# ESP-12E_Dev_Board_with_level_shifter.net
KiCad netlist of a schematic drawn in EAGLE
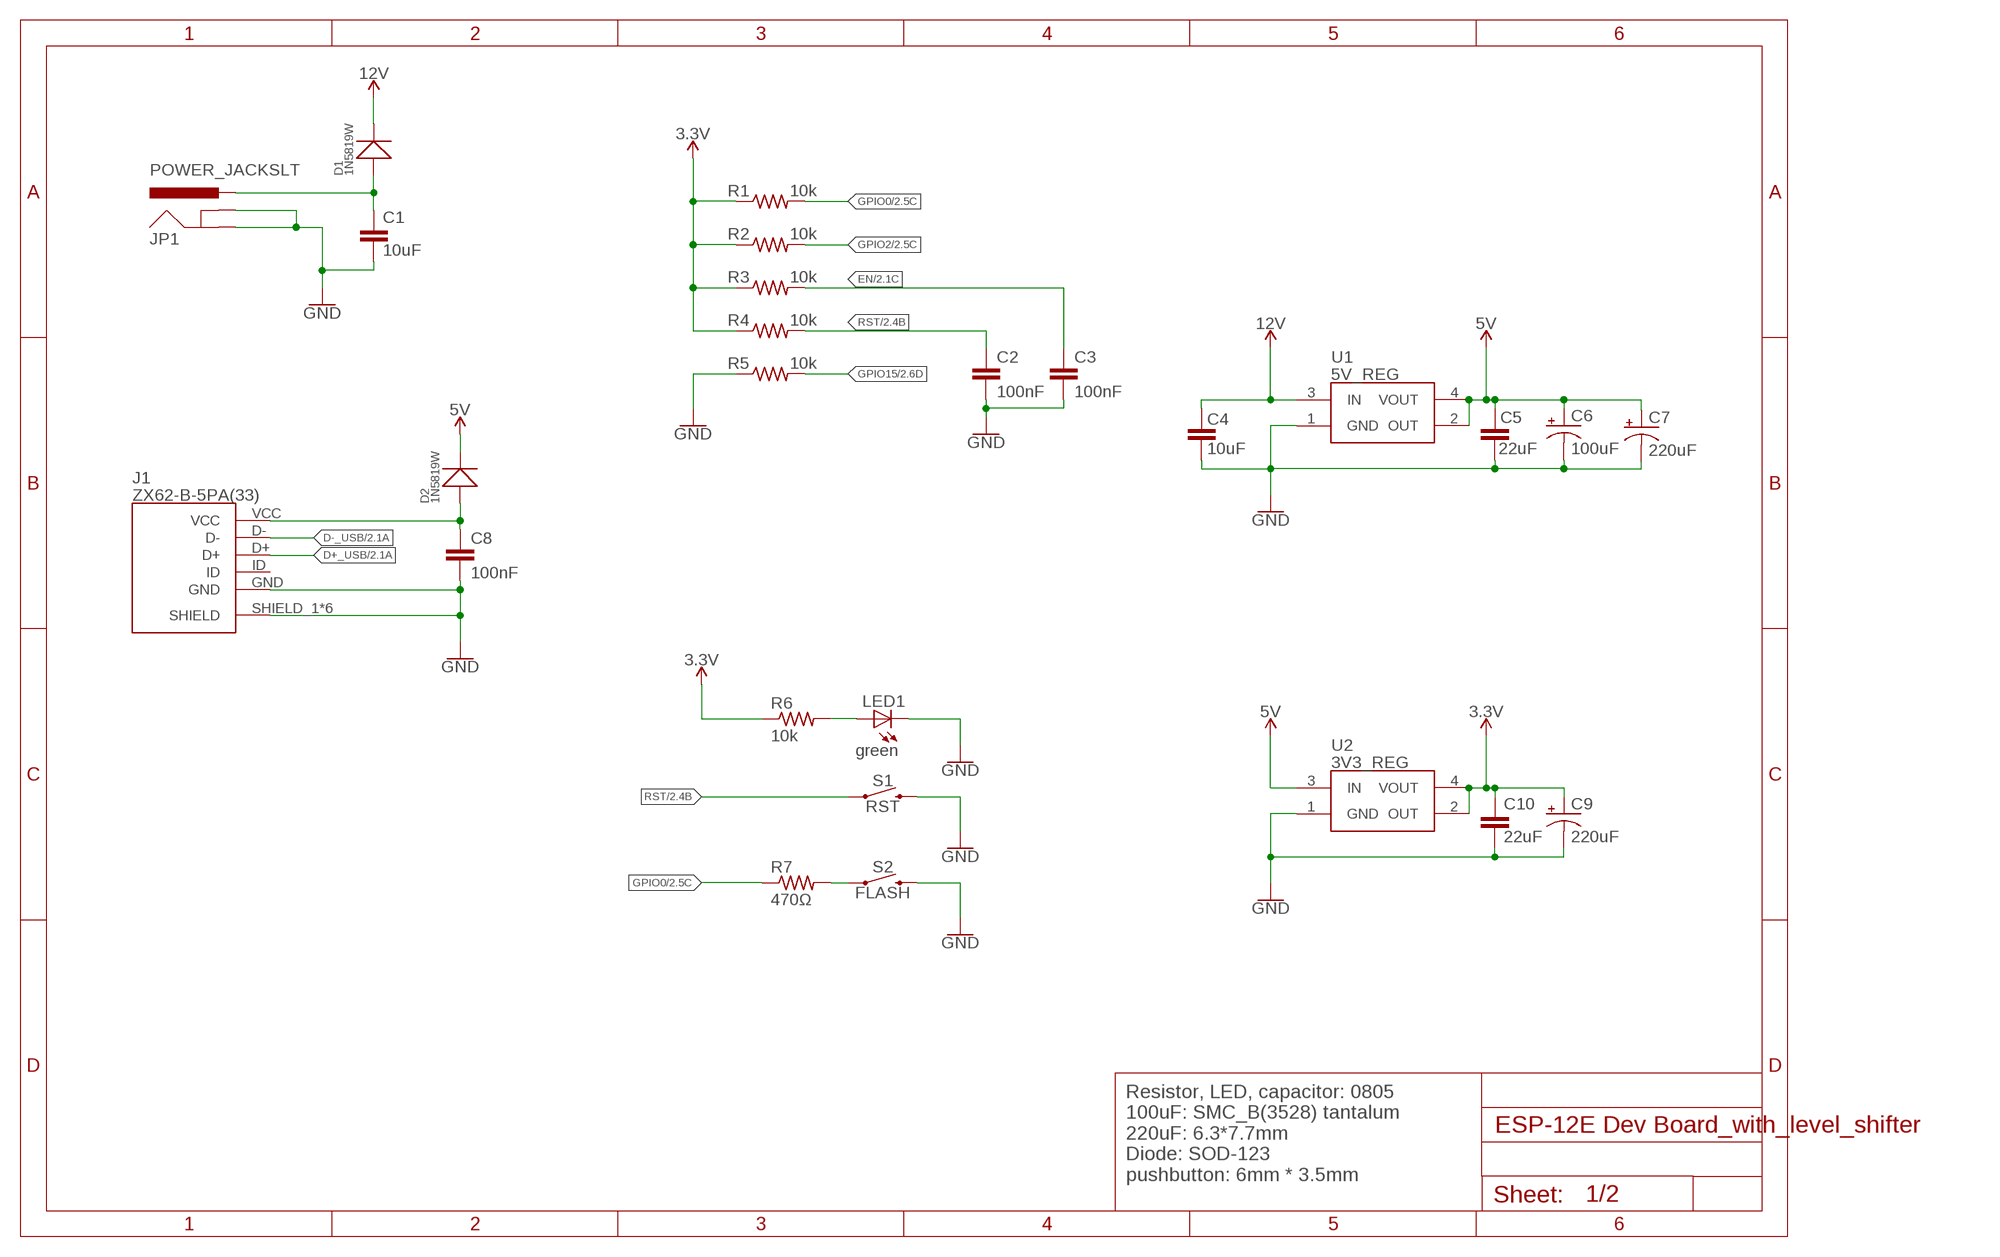
[diagram p0: schematic, sheet 1]
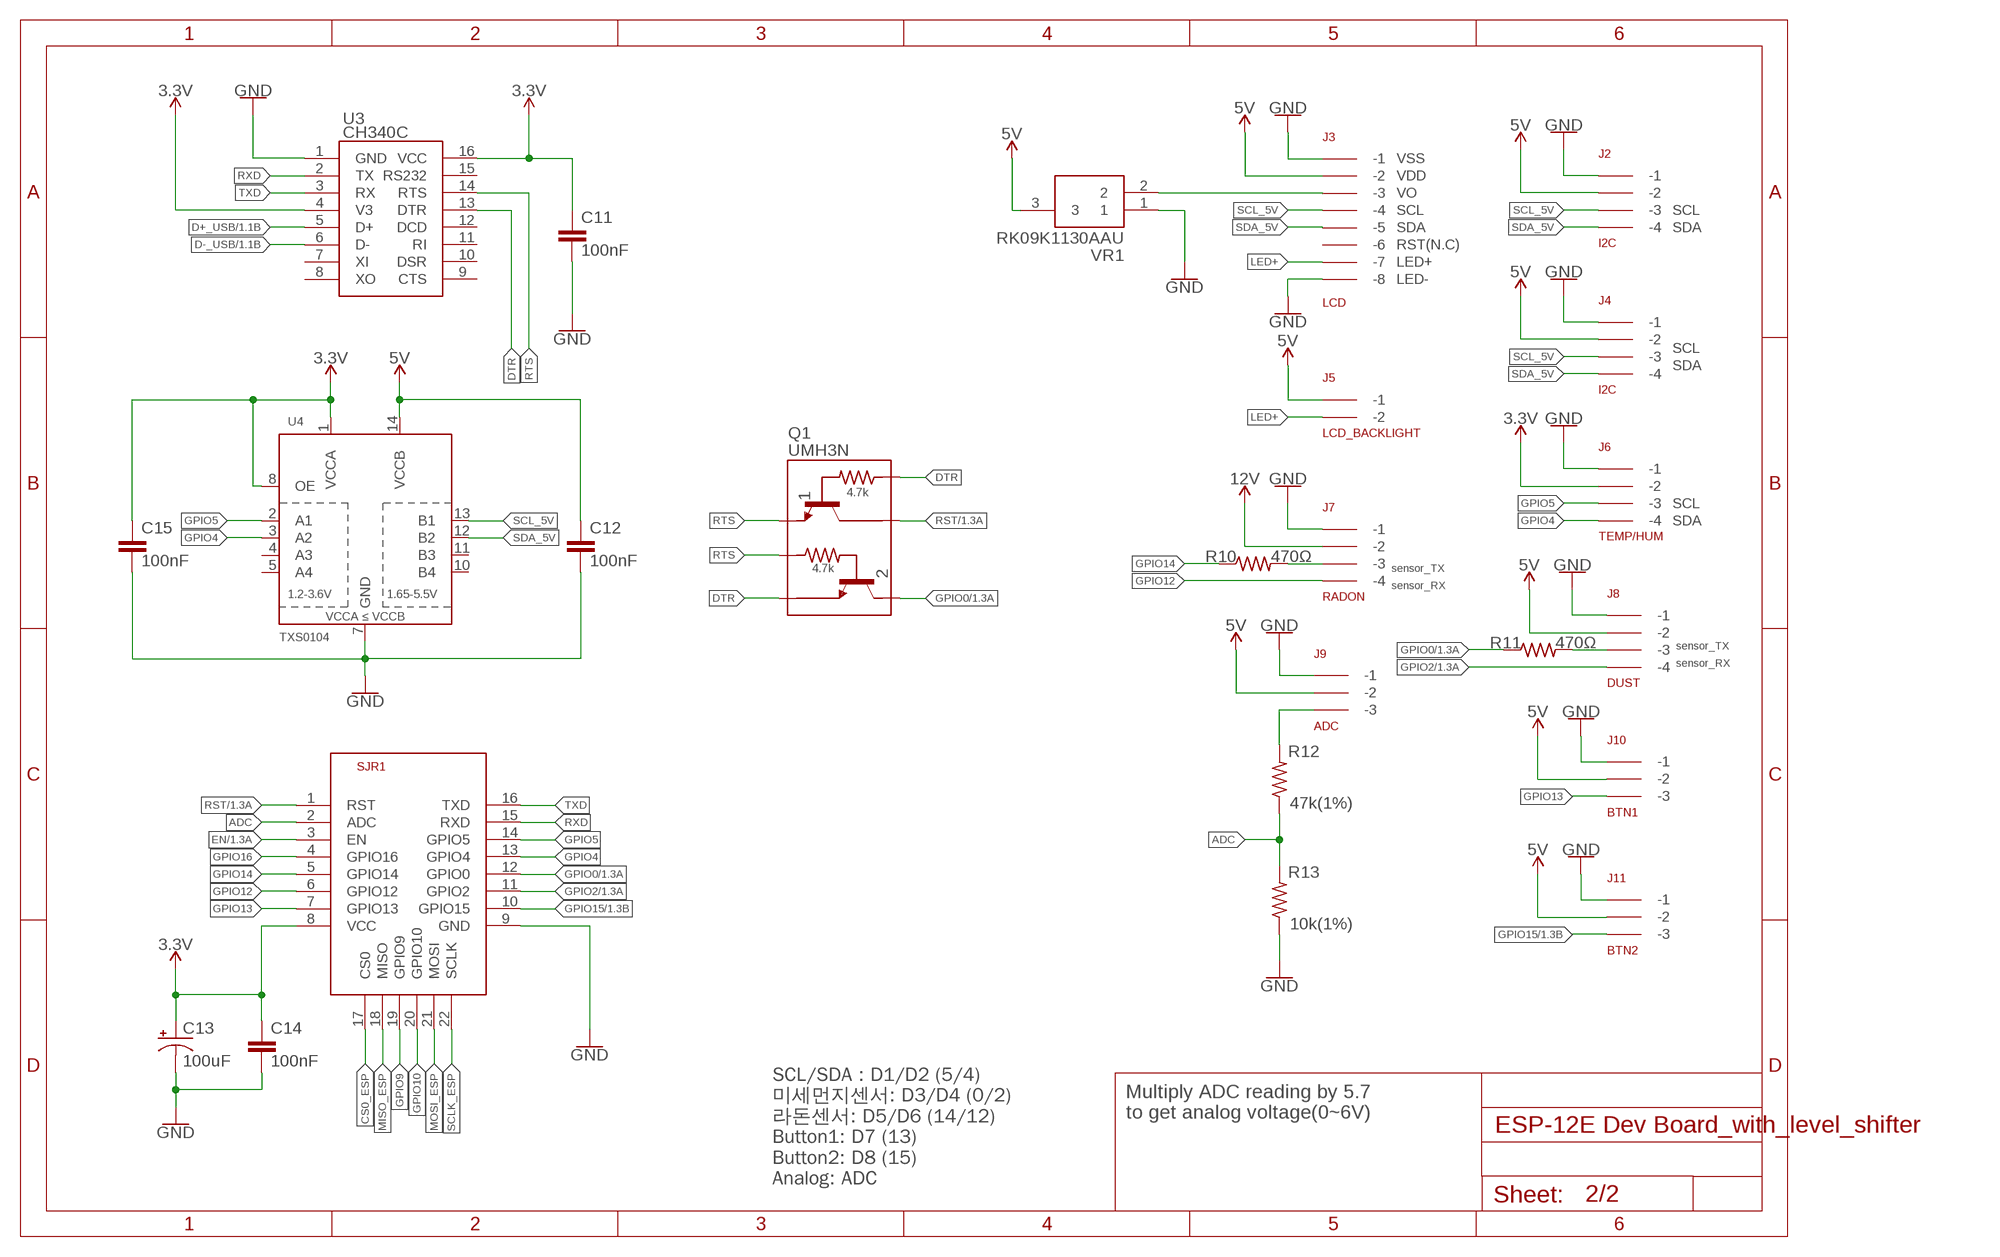
[diagram p1: schematic, sheet 2]

(export (version "E")
  (design (tool "Eeschema 10.0.6"))
  (components
    (comp (ref "C1")
      (value "10uF")
      (footprint "eagle-import:C0805")
      (libsource (lib "eagle-import") (part "C-EUC0805"))
    )
    (comp (ref "C2")
      (value "100nF")
      (footprint "eagle-import:C0805")
      (libsource (lib "eagle-import") (part "C-EUC0805"))
    )
    (comp (ref "C3")
      (value "100nF")
      (footprint "eagle-import:C0805")
      (libsource (lib "eagle-import") (part "C-EUC0805"))
    )
    (comp (ref "C4")
      (value "10uF")
      (footprint "eagle-import:C0805")
      (libsource (lib "eagle-import") (part "C-EUC0805"))
    )
    (comp (ref "C5")
      (value "22uF")
      (footprint "eagle-import:C0805")
      (libsource (lib "eagle-import") (part "C-EUC0805"))
    )
    (comp (ref "C6")
      (value "100uF")
      (footprint "eagle-import:SMC_B")
      (libsource (lib "eagle-import") (part "CPOL-USSMCB"))
    )
    (comp (ref "C7")
      (value "220uF")
      (footprint "eagle-import:UD-6,3X7,7_NICHICON")
      (libsource (lib "eagle-import") (part "CPOL-USUD-6,3X7,7"))
    )
    (comp (ref "C8")
      (value "100nF")
      (footprint "eagle-import:C0805")
      (libsource (lib "eagle-import") (part "C-EUC0805"))
    )
    (comp (ref "C9")
      (value "220uF")
      (footprint "eagle-import:UD-6,3X7,7_NICHICON")
      (libsource (lib "eagle-import") (part "CPOL-USUD-6,3X7,7"))
    )
    (comp (ref "C10")
      (value "22uF")
      (footprint "eagle-import:C0805")
      (libsource (lib "eagle-import") (part "C-EUC0805"))
    )
    (comp (ref "D1")
      (value "1N5819W")
      (footprint "eagle-import:SOD-123")
      (fields (field (name "MPN") "SS0520-7-F"))
      (libsource (lib "eagle-import") (part "SMD-DIODE-SCHOTTKY-20V-500MA(SOD-123)"))
    )
    (comp (ref "D2")
      (value "1N5819W")
      (footprint "eagle-import:SOD-123")
      (fields (field (name "MPN") "SS0520-7-F"))
      (libsource (lib "eagle-import") (part "SMD-DIODE-SCHOTTKY-20V-500MA(SOD-123)"))
    )
    (comp (ref "J1")
      (value "ZX62-B-5PA(33)")
      (footprint "eagle-import:ZX62B5PA33")
      (fields (field (name "MOUSER_PART_NUMBER") "798-ZX62-B-5PA33"))
      (libsource (lib "eagle-import") (part "ZX62-B-5PA(33)"))
    )
    (comp (ref "JP1")
      (value "POWER_JACKSLT")
      (footprint "eagle-import:POWER_JACK_SLOT")
      (libsource (lib "eagle-import") (part "POWER_JACKSLT"))
    )
    (comp (ref "LED1")
      (value "green")
      (footprint "eagle-import:CHIP-LED0805")
      (libsource (lib "eagle-import") (part "LEDCHIP-LED0805"))
    )
    (comp (ref "R1")
      (value "10k")
      (footprint "eagle-import:R0805")
      (libsource (lib "eagle-import") (part "R-US_R0805"))
    )
    (comp (ref "R2")
      (value "10k")
      (footprint "eagle-import:R0805")
      (libsource (lib "eagle-import") (part "R-US_R0805"))
    )
    (comp (ref "R3")
      (value "10k")
      (footprint "eagle-import:R0805")
      (libsource (lib "eagle-import") (part "R-US_R0805"))
    )
    (comp (ref "R4")
      (value "10k")
      (footprint "eagle-import:R0805")
      (libsource (lib "eagle-import") (part "R-US_R0805"))
    )
    (comp (ref "R5")
      (value "10k")
      (footprint "eagle-import:R0805")
      (libsource (lib "eagle-import") (part "R-US_R0805"))
    )
    (comp (ref "R6")
      (value "10k")
      (footprint "eagle-import:R0805")
      (libsource (lib "eagle-import") (part "R-US_R0805"))
    )
    (comp (ref "R7")
      (value "470Ω")
      (footprint "eagle-import:R0805")
      (libsource (lib "eagle-import") (part "R-US_R0805"))
    )
    (comp (ref "S1")
      (value "RST")
      (footprint "eagle-import:TACTILE_SWITCH_SMD_6.0X3.5MM")
      (libsource (lib "eagle-import") (part "MOMENTARY-SWITCH-SPST-SMD-6.0X3.5MM"))
    )
    (comp (ref "S2")
      (value "FLASH")
      (footprint "eagle-import:TACTILE_SWITCH_SMD_6.0X3.5MM")
      (libsource (lib "eagle-import") (part "MOMENTARY-SWITCH-SPST-SMD-6.0X3.5MM"))
    )
    (comp (ref "U1")
      (value "5V_REG")
      (footprint "eagle-import:SOT230P700X170-4N")
      (fields
        (field (name "MANUFACTURER_PART_NUMBER") "AZ1117H-5.0TRE1")
        (field (name "MOUSER_PART_NUMBER") "621-AZ1117H-5.0TRE1")
      )
      (libsource (lib "eagle-import") (part "AZ1117H-5.0TRE1"))
    )
    (comp (ref "U2")
      (value "3V3_REG")
      (footprint "eagle-import:SOT230P700X170-4N")
      (fields
        (field (name "MANUFACTURER_PART_NUMBER") "AZ1117H-5.0TRE1")
        (field (name "MOUSER_PART_NUMBER") "621-AZ1117H-5.0TRE1")
      )
      (libsource (lib "eagle-import") (part "AZ1117H-5.0TRE1"))
    )
    (comp (ref "C11")
      (value "100nF")
      (footprint "eagle-import:C0805")
      (libsource (lib "eagle-import") (part "C-EUC0805"))
    )
    (comp (ref "C12")
      (value "100nF")
      (footprint "eagle-import:C0805")
      (libsource (lib "eagle-import") (part "C-EUC0805"))
    )
    (comp (ref "C13")
      (value "100uF")
      (footprint "eagle-import:SMC_B")
      (libsource (lib "eagle-import") (part "CPOL-USSMCB"))
    )
    (comp (ref "C14")
      (value "100nF")
      (footprint "eagle-import:C0805")
      (libsource (lib "eagle-import") (part "C-EUC0805"))
    )
    (comp (ref "C15")
      (value "100nF")
      (footprint "eagle-import:C0805")
      (libsource (lib "eagle-import") (part "C-EUC0805"))
    )
    (comp (ref "J2")
      (value "I2C")
      (footprint "eagle-import:5267-4")
      (libsource (lib "eagle-import") (part "5267-4"))
    )
    (comp (ref "J3")
      (value "LCD")
      (footprint "eagle-import:5267-8")
      (libsource (lib "eagle-import") (part "5267-8"))
    )
    (comp (ref "J4")
      (value "I2C")
      (footprint "eagle-import:5267-4")
      (libsource (lib "eagle-import") (part "5267-4"))
    )
    (comp (ref "J5")
      (value "LCD_BACKLIGHT")
      (footprint "eagle-import:5267-2")
      (libsource (lib "eagle-import") (part "5267-2"))
    )
    (comp (ref "J6")
      (value "TEMP/HUM")
      (footprint "eagle-import:5267-4")
      (libsource (lib "eagle-import") (part "5267-4"))
    )
    (comp (ref "J7")
      (value "RADON")
      (footprint "eagle-import:5267-4")
      (libsource (lib "eagle-import") (part "5267-4"))
    )
    (comp (ref "J8")
      (value "DUST")
      (footprint "eagle-import:5267-4")
      (libsource (lib "eagle-import") (part "5267-4"))
    )
    (comp (ref "J9")
      (value "ADC")
      (footprint "eagle-import:5267-3")
      (libsource (lib "eagle-import") (part "5267-3"))
    )
    (comp (ref "J10")
      (value "BTN1")
      (footprint "eagle-import:5267-3")
      (libsource (lib "eagle-import") (part "5267-3"))
    )
    (comp (ref "J11")
      (value "BTN2")
      (footprint "eagle-import:5267-3")
      (libsource (lib "eagle-import") (part "5267-3"))
    )
    (comp (ref "Q1")
      (value "UMH3N")
      (footprint "eagle-import:SOT65P210X100-6N")
      (fields
        (field (name "MANUFACTURER_PART_NUMBER") "UMH3NFHATN")
        (field (name "MOUSER_PART_NUMBER") "755-UMH3NFHATN")
      )
      (libsource (lib "eagle-import") (part "UMH3NFHATN"))
    )
    (comp (ref "R10")
      (value "470Ω")
      (footprint "eagle-import:R0805")
      (libsource (lib "eagle-import") (part "R-US_R0805"))
    )
    (comp (ref "R11")
      (value "470Ω")
      (footprint "eagle-import:R0805")
      (libsource (lib "eagle-import") (part "R-US_R0805"))
    )
    (comp (ref "R12")
      (value "47k(1%)")
      (footprint "eagle-import:R0805")
      (libsource (lib "eagle-import") (part "R-US_R0805"))
    )
    (comp (ref "R13")
      (value "10k(1%)")
      (footprint "eagle-import:R0805")
      (libsource (lib "eagle-import") (part "R-US_R0805"))
    )
    (comp (ref "SJR1")
      (value "ESP-12E")
      (footprint "eagle-import:ESP8266-ESP12E")
      (libsource (lib "eagle-import") (part "ESP8266-12EESP12E"))
    )
    (comp (ref "U3")
      (value "CH340C")
      (footprint "eagle-import:SOIC16")
      (libsource (lib "eagle-import") (part "CH340G"))
    )
    (comp (ref "U4")
      (value "TXS0104")
      (footprint "eagle-import:TSSOP14")
      (libsource (lib "eagle-import") (part "TXB0104PWR"))
    )
    (comp (ref "VR1")
      (value "RK09K1130AAU")
      (footprint "eagle-import:RK09K1130BGM")
      (fields
        (field (name "MANUFACTURER_PART_NUMBER") "RK09K1130A6S")
        (field (name "MOUSER_PART_NUMBER") "688-RK09K1130A6S")
      )
      (libsource (lib "eagle-import") (part "RK09K1130A6S"))
    )
  )
  (nets
    (net (code "1") (name "3.3V") (class "Default")
      (node (ref "C10") (pin "2") (pinfunction "2_2") (pintype "passive"))
      (node (ref "C11") (pin "2") (pinfunction "2_2") (pintype "passive"))
      (node (ref "C13") (pin "+") (pinfunction "+_+") (pintype "passive"))
      (node (ref "C14") (pin "2") (pinfunction "2_2") (pintype "passive"))
      (node (ref "C15") (pin "2") (pinfunction "2_2") (pintype "passive"))
      (node (ref "C9") (pin "+") (pinfunction "+_+") (pintype "passive"))
      (node (ref "J6") (pin "P$2") (pinfunction "-2_P$2") (pintype "bidirectional"))
      (node (ref "R1") (pin "1") (pinfunction "1_1") (pintype "passive"))
      (node (ref "R2") (pin "1") (pinfunction "1_1") (pintype "passive"))
      (node (ref "R3") (pin "1") (pinfunction "1_1") (pintype "passive"))
      (node (ref "R4") (pin "1") (pinfunction "1_1") (pintype "passive"))
      (node (ref "R6") (pin "1") (pinfunction "1_1") (pintype "passive"))
      (node (ref "SJR1") (pin "8") (pinfunction "VCC_8") (pintype "bidirectional"))
      (node (ref "U2") (pin "2") (pinfunction "OUT_2") (pintype "bidirectional"))
      (node (ref "U2") (pin "4") (pinfunction "VOUT_4") (pintype "bidirectional"))
      (node (ref "U3") (pin "16") (pinfunction "VCC_16") (pintype "bidirectional"))
      (node (ref "U3") (pin "4") (pinfunction "V3_4") (pintype "bidirectional"))
      (node (ref "U4") (pin "1") (pinfunction "VCCA_1") (pintype "bidirectional"))
      (node (ref "U4") (pin "8") (pinfunction "OE_8") (pintype "bidirectional"))
    )
    (net (code "2") (name "5V") (class "Default")
      (node (ref "C12") (pin "2") (pinfunction "2_2") (pintype "passive"))
      (node (ref "C5") (pin "1") (pinfunction "1_1") (pintype "passive"))
      (node (ref "C6") (pin "+") (pinfunction "+_+") (pintype "passive"))
      (node (ref "C7") (pin "+") (pinfunction "+_+") (pintype "passive"))
      (node (ref "D2") (pin "-") (pinfunction "-_-") (pintype "passive"))
      (node (ref "J10") (pin "P$2") (pinfunction "-2_P$2") (pintype "bidirectional"))
      (node (ref "J11") (pin "P$2") (pinfunction "-2_P$2") (pintype "bidirectional"))
      (node (ref "J2") (pin "P$2") (pinfunction "-2_P$2") (pintype "bidirectional"))
      (node (ref "J3") (pin "P$2") (pinfunction "-2_P$2") (pintype "bidirectional"))
      (node (ref "J4") (pin "P$2") (pinfunction "-2_P$2") (pintype "bidirectional"))
      (node (ref "J5") (pin "P$1") (pinfunction "-1_P$1") (pintype "bidirectional"))
      (node (ref "J8") (pin "P$2") (pinfunction "-2_P$2") (pintype "bidirectional"))
      (node (ref "J9") (pin "P$2") (pinfunction "-2_P$2") (pintype "bidirectional"))
      (node (ref "U1") (pin "2") (pinfunction "OUT_2") (pintype "bidirectional"))
      (node (ref "U1") (pin "4") (pinfunction "VOUT_4") (pintype "bidirectional"))
      (node (ref "U2") (pin "3") (pinfunction "IN_3") (pintype "bidirectional"))
      (node (ref "U4") (pin "14") (pinfunction "VCCB_14") (pintype "bidirectional"))
      (node (ref "VR1") (pin "3") (pinfunction "3_3") (pintype "bidirectional"))
    )
    (net (code "3") (name "12V") (class "Default")
      (node (ref "C4") (pin "1") (pinfunction "1_1") (pintype "passive"))
      (node (ref "D1") (pin "-") (pinfunction "-_-") (pintype "passive"))
      (node (ref "J7") (pin "P$2") (pinfunction "-2_P$2") (pintype "bidirectional"))
      (node (ref "U1") (pin "3") (pinfunction "IN_3") (pintype "bidirectional"))
    )
    (net (code "4") (name "ADC") (class "Default")
      (node (ref "R12") (pin "1") (pinfunction "1_1") (pintype "passive"))
      (node (ref "R13") (pin "2") (pinfunction "2_2") (pintype "passive"))
      (node (ref "SJR1") (pin "2") (pinfunction "ADC_2") (pintype "bidirectional"))
    )
    (net (code "5") (name "CS0_ESP") (class "Default")
      (node (ref "SJR1") (pin "17") (pinfunction "CS0_17") (pintype "bidirectional"))
    )
    (net (code "6") (name "D+_USB") (class "Default")
      (node (ref "J1") (pin "D+") (pinfunction "D+_D+") (pintype "bidirectional"))
      (node (ref "U3") (pin "5") (pinfunction "D+_5") (pintype "bidirectional"))
    )
    (net (code "7") (name "D-_USB") (class "Default")
      (node (ref "J1") (pin "D-") (pinfunction "D-_D-") (pintype "bidirectional"))
      (node (ref "U3") (pin "6") (pinfunction "D-_6") (pintype "bidirectional"))
    )
    (net (code "8") (name "DTR") (class "Default")
      (node (ref "Q1") (pin "2") (pinfunction "2_2") (pintype "bidirectional"))
      (node (ref "Q1") (pin "4") (pinfunction "4_4") (pintype "bidirectional"))
      (node (ref "U3") (pin "13") (pinfunction "DTR_13") (pintype "bidirectional"))
    )
    (net (code "9") (name "EN") (class "Default")
      (node (ref "C3") (pin "2") (pinfunction "2_2") (pintype "passive"))
      (node (ref "R3") (pin "2") (pinfunction "2_2") (pintype "passive"))
      (node (ref "SJR1") (pin "3") (pinfunction "EN_3") (pintype "bidirectional"))
    )
    (net (code "10") (name "GND") (class "Default")
      (node (ref "C1") (pin "1") (pinfunction "1_1") (pintype "passive"))
      (node (ref "C10") (pin "1") (pinfunction "1_1") (pintype "passive"))
      (node (ref "C11") (pin "1") (pinfunction "1_1") (pintype "passive"))
      (node (ref "C12") (pin "1") (pinfunction "1_1") (pintype "passive"))
      (node (ref "C13") (pin "-") (pinfunction "-_-") (pintype "passive"))
      (node (ref "C14") (pin "1") (pinfunction "1_1") (pintype "passive"))
      (node (ref "C15") (pin "1") (pinfunction "1_1") (pintype "passive"))
      (node (ref "C2") (pin "1") (pinfunction "1_1") (pintype "passive"))
      (node (ref "C3") (pin "1") (pinfunction "1_1") (pintype "passive"))
      (node (ref "C4") (pin "2") (pinfunction "2_2") (pintype "passive"))
      (node (ref "C5") (pin "2") (pinfunction "2_2") (pintype "passive"))
      (node (ref "C6") (pin "-") (pinfunction "-_-") (pintype "passive"))
      (node (ref "C7") (pin "-") (pinfunction "-_-") (pintype "passive"))
      (node (ref "C8") (pin "1") (pinfunction "1_1") (pintype "passive"))
      (node (ref "C9") (pin "-") (pinfunction "-_-") (pintype "passive"))
      (node (ref "J1") (pin "GND") (pinfunction "GND_GND") (pintype "bidirectional"))
      (node (ref "J1") (pin "SHIELD_1") (pinfunction "SHIELD_SHIELD_1") (pintype "bidirectional"))
      (node (ref "J1") (pin "SHIELD_2") (pinfunction "SHIELD_SHIELD_2") (pintype "bidirectional"))
      (node (ref "J1") (pin "SHIELD_3") (pinfunction "SHIELD_SHIELD_3") (pintype "bidirectional"))
      (node (ref "J1") (pin "SHIELD_4") (pinfunction "SHIELD_SHIELD_4") (pintype "bidirectional"))
      (node (ref "J1") (pin "SHIELD_5") (pinfunction "SHIELD_SHIELD_5") (pintype "bidirectional"))
      (node (ref "J1") (pin "SHIELD_6") (pinfunction "SHIELD_SHIELD_6") (pintype "bidirectional"))
      (node (ref "J10") (pin "P$1") (pinfunction "-1_P$1") (pintype "bidirectional"))
      (node (ref "J11") (pin "P$1") (pinfunction "-1_P$1") (pintype "bidirectional"))
      (node (ref "J2") (pin "P$1") (pinfunction "-1_P$1") (pintype "bidirectional"))
      (node (ref "J3") (pin "P$1") (pinfunction "-1_P$1") (pintype "bidirectional"))
      (node (ref "J3") (pin "P$8") (pinfunction "-8_P$8") (pintype "bidirectional"))
      (node (ref "J4") (pin "P$1") (pinfunction "-1_P$1") (pintype "bidirectional"))
      (node (ref "J6") (pin "P$1") (pinfunction "-1_P$1") (pintype "bidirectional"))
      (node (ref "J7") (pin "P$1") (pinfunction "-1_P$1") (pintype "bidirectional"))
      (node (ref "J8") (pin "P$1") (pinfunction "-1_P$1") (pintype "bidirectional"))
      (node (ref "J9") (pin "P$1") (pinfunction "-1_P$1") (pintype "bidirectional"))
      (node (ref "JP1") (pin "GND@1") (pinfunction "GNDBREAK_GND@1") (pintype "power_in"))
      (node (ref "JP1") (pin "GND@2") (pinfunction "GND_GND@2") (pintype "power_in"))
      (node (ref "LED1") (pin "C") (pinfunction "C_C") (pintype "passive"))
      (node (ref "R13") (pin "1") (pinfunction "1_1") (pintype "passive"))
      (node (ref "R5") (pin "1") (pinfunction "1_1") (pintype "passive"))
      (node (ref "S1") (pin "2") (pinfunction "2_2") (pintype "passive"))
      (node (ref "S2") (pin "2") (pinfunction "2_2") (pintype "passive"))
      (node (ref "SJR1") (pin "9") (pinfunction "GND_9") (pintype "bidirectional"))
      (node (ref "U1") (pin "1") (pinfunction "GND_1") (pintype "bidirectional"))
      (node (ref "U2") (pin "1") (pinfunction "GND_1") (pintype "bidirectional"))
      (node (ref "U3") (pin "1") (pinfunction "GND_1") (pintype "bidirectional"))
      (node (ref "U4") (pin "7") (pinfunction "GND_7") (pintype "bidirectional"))
      (node (ref "VR1") (pin "1") (pinfunction "1_1") (pintype "bidirectional"))
    )
    (net (code "11") (name "GPIO0") (class "Default")
      (node (ref "Q1") (pin "3") (pinfunction "3_3") (pintype "bidirectional"))
      (node (ref "R1") (pin "2") (pinfunction "2_2") (pintype "passive"))
      (node (ref "R11") (pin "1") (pinfunction "1_1") (pintype "passive"))
      (node (ref "R7") (pin "1") (pinfunction "1_1") (pintype "passive"))
      (node (ref "SJR1") (pin "12") (pinfunction "GPIO0_12") (pintype "bidirectional"))
    )
    (net (code "12") (name "GPIO2") (class "Default")
      (node (ref "J8") (pin "P$4") (pinfunction "-4_P$4") (pintype "bidirectional"))
      (node (ref "R2") (pin "2") (pinfunction "2_2") (pintype "passive"))
      (node (ref "SJR1") (pin "11") (pinfunction "GPIO2_11") (pintype "bidirectional"))
    )
    (net (code "13") (name "GPIO4") (class "Default")
      (node (ref "J6") (pin "P$4") (pinfunction "-4_P$4") (pintype "bidirectional"))
      (node (ref "SJR1") (pin "13") (pinfunction "GPIO4_13") (pintype "bidirectional"))
      (node (ref "U4") (pin "3") (pinfunction "A2_3") (pintype "bidirectional"))
    )
    (net (code "14") (name "GPIO5") (class "Default")
      (node (ref "J6") (pin "P$3") (pinfunction "-3_P$3") (pintype "bidirectional"))
      (node (ref "SJR1") (pin "14") (pinfunction "GPIO5_14") (pintype "bidirectional"))
      (node (ref "U4") (pin "2") (pinfunction "A1_2") (pintype "bidirectional"))
    )
    (net (code "15") (name "GPIO9") (class "Default")
      (node (ref "SJR1") (pin "19") (pinfunction "GPIO9_19") (pintype "bidirectional"))
    )
    (net (code "16") (name "GPIO10") (class "Default")
      (node (ref "SJR1") (pin "20") (pinfunction "GPIO10_20") (pintype "bidirectional"))
    )
    (net (code "17") (name "GPIO12") (class "Default")
      (node (ref "J7") (pin "P$4") (pinfunction "-4_P$4") (pintype "bidirectional"))
      (node (ref "SJR1") (pin "6") (pinfunction "GPIO12_6") (pintype "bidirectional"))
    )
    (net (code "18") (name "GPIO13") (class "Default")
      (node (ref "J10") (pin "P$3") (pinfunction "-3_P$3") (pintype "bidirectional"))
      (node (ref "SJR1") (pin "7") (pinfunction "GPIO13_7") (pintype "bidirectional"))
    )
    (net (code "19") (name "GPIO14") (class "Default")
      (node (ref "R10") (pin "1") (pinfunction "1_1") (pintype "passive"))
      (node (ref "SJR1") (pin "5") (pinfunction "GPIO14_5") (pintype "bidirectional"))
    )
    (net (code "20") (name "GPIO15") (class "Default")
      (node (ref "J11") (pin "P$3") (pinfunction "-3_P$3") (pintype "bidirectional"))
      (node (ref "R5") (pin "2") (pinfunction "2_2") (pintype "passive"))
      (node (ref "SJR1") (pin "10") (pinfunction "GPIO15_10") (pintype "bidirectional"))
    )
    (net (code "21") (name "GPIO16") (class "Default")
      (node (ref "SJR1") (pin "4") (pinfunction "GPIO16_4") (pintype "bidirectional"))
    )
    (net (code "22") (name "LED+") (class "Default")
      (node (ref "J3") (pin "P$7") (pinfunction "-7_P$7") (pintype "bidirectional"))
      (node (ref "J5") (pin "P$2") (pinfunction "-2_P$2") (pintype "bidirectional"))
    )
    (net (code "23") (name "MISO_ESP") (class "Default")
      (node (ref "SJR1") (pin "18") (pinfunction "MISO_18") (pintype "bidirectional"))
    )
    (net (code "24") (name "MOSI_ESP") (class "Default")
      (node (ref "SJR1") (pin "21") (pinfunction "MOSI_21") (pintype "bidirectional"))
    )
    (net (code "25") (name "Net-(C1-Pad2)") (class "Default")
      (node (ref "C1") (pin "2") (pinfunction "2_2") (pintype "passive"))
      (node (ref "D1") (pin "+") (pinfunction "+_+") (pintype "passive"))
      (node (ref "JP1") (pin "PWR") (pinfunction "PWR_PWR") (pintype "power_in"))
    )
    (net (code "26") (name "Net-(C8-Pad2)") (class "Default")
      (node (ref "C8") (pin "2") (pinfunction "2_2") (pintype "passive"))
      (node (ref "D2") (pin "+") (pinfunction "+_+") (pintype "passive"))
      (node (ref "J1") (pin "VCC") (pinfunction "VCC_VCC") (pintype "bidirectional"))
    )
    (net (code "27") (name "Net-(J3--3)") (class "Default")
      (node (ref "J3") (pin "P$3") (pinfunction "-3_P$3") (pintype "bidirectional"))
      (node (ref "VR1") (pin "2") (pinfunction "2_2") (pintype "bidirectional"))
    )
    (net (code "28") (name "Net-(J7--3)") (class "Default")
      (node (ref "J7") (pin "P$3") (pinfunction "-3_P$3") (pintype "bidirectional"))
      (node (ref "R10") (pin "2") (pinfunction "2_2") (pintype "passive"))
    )
    (net (code "29") (name "Net-(J8--3)") (class "Default")
      (node (ref "J8") (pin "P$3") (pinfunction "-3_P$3") (pintype "bidirectional"))
      (node (ref "R11") (pin "2") (pinfunction "2_2") (pintype "passive"))
    )
    (net (code "30") (name "Net-(J9--3)") (class "Default")
      (node (ref "J9") (pin "P$3") (pinfunction "-3_P$3") (pintype "bidirectional"))
      (node (ref "R12") (pin "2") (pinfunction "2_2") (pintype "passive"))
    )
    (net (code "31") (name "Net-(LED1-PadA)") (class "Default")
      (node (ref "LED1") (pin "A") (pinfunction "A_A") (pintype "passive"))
      (node (ref "R6") (pin "2") (pinfunction "2_2") (pintype "passive"))
    )
    (net (code "32") (name "Net-(R7-Pad2)") (class "Default")
      (node (ref "R7") (pin "2") (pinfunction "2_2") (pintype "passive"))
      (node (ref "S2") (pin "1") (pinfunction "1_1") (pintype "passive"))
    )
    (net (code "33") (name "RST") (class "Default")
      (node (ref "C2") (pin "2") (pinfunction "2_2") (pintype "passive"))
      (node (ref "Q1") (pin "6") (pinfunction "6_6") (pintype "bidirectional"))
      (node (ref "R4") (pin "2") (pinfunction "2_2") (pintype "passive"))
      (node (ref "S1") (pin "1") (pinfunction "1_1") (pintype "passive"))
      (node (ref "SJR1") (pin "1") (pinfunction "RST_1") (pintype "bidirectional"))
    )
    (net (code "34") (name "RTS") (class "Default")
      (node (ref "Q1") (pin "1") (pinfunction "1_1") (pintype "bidirectional"))
      (node (ref "Q1") (pin "5") (pinfunction "5_5") (pintype "bidirectional"))
      (node (ref "U3") (pin "14") (pinfunction "RTS_14") (pintype "bidirectional"))
    )
    (net (code "35") (name "RXD") (class "Default")
      (node (ref "SJR1") (pin "15") (pinfunction "RXD_15") (pintype "bidirectional"))
      (node (ref "U3") (pin "2") (pinfunction "TX_2") (pintype "bidirectional"))
    )
    (net (code "36") (name "SCLK_ESP") (class "Default")
      (node (ref "SJR1") (pin "22") (pinfunction "SCLK_22") (pintype "bidirectional"))
    )
    (net (code "37") (name "SCL_5V") (class "Default")
      (node (ref "J2") (pin "P$3") (pinfunction "-3_P$3") (pintype "bidirectional"))
      (node (ref "J3") (pin "P$4") (pinfunction "-4_P$4") (pintype "bidirectional"))
      (node (ref "J4") (pin "P$3") (pinfunction "-3_P$3") (pintype "bidirectional"))
      (node (ref "U4") (pin "13") (pinfunction "B1_13") (pintype "bidirectional"))
    )
    (net (code "38") (name "SDA_5V") (class "Default")
      (node (ref "J2") (pin "P$4") (pinfunction "-4_P$4") (pintype "bidirectional"))
      (node (ref "J3") (pin "P$5") (pinfunction "-5_P$5") (pintype "bidirectional"))
      (node (ref "J4") (pin "P$4") (pinfunction "-4_P$4") (pintype "bidirectional"))
      (node (ref "U4") (pin "12") (pinfunction "B2_12") (pintype "bidirectional"))
    )
    (net (code "39") (name "TXD") (class "Default")
      (node (ref "SJR1") (pin "16") (pinfunction "TXD_16") (pintype "bidirectional"))
      (node (ref "U3") (pin "3") (pinfunction "RX_3") (pintype "bidirectional"))
    )
    (net (code "40") (name "unconnected-(J1-PadID)") (class "Default")
      (node (ref "J1") (pin "ID") (pinfunction "ID_ID") (pintype "bidirectional"))
    )
    (net (code "41") (name "unconnected-(J3--6-PadP$6)") (class "Default")
      (node (ref "J3") (pin "P$6") (pinfunction "-6_P$6") (pintype "bidirectional"))
    )
    (net (code "42") (name "unconnected-(U3-CTS-Pad9)") (class "Default")
      (node (ref "U3") (pin "9") (pinfunction "CTS_9") (pintype "bidirectional"))
    )
    (net (code "43") (name "unconnected-(U3-DCD-Pad12)") (class "Default")
      (node (ref "U3") (pin "12") (pinfunction "DCD_12") (pintype "bidirectional"))
    )
    (net (code "44") (name "unconnected-(U3-DSR-Pad10)") (class "Default")
      (node (ref "U3") (pin "10") (pinfunction "DSR_10") (pintype "bidirectional"))
    )
    (net (code "45") (name "unconnected-(U3-RI-Pad11)") (class "Default")
      (node (ref "U3") (pin "11") (pinfunction "RI_11") (pintype "bidirectional"))
    )
    (net (code "46") (name "unconnected-(U3-RS232-Pad15)") (class "Default")
      (node (ref "U3") (pin "15") (pinfunction "RS232_15") (pintype "bidirectional"))
    )
    (net (code "47") (name "unconnected-(U3-XI-Pad7)") (class "Default")
      (node (ref "U3") (pin "7") (pinfunction "XI_7") (pintype "bidirectional"))
    )
    (net (code "48") (name "unconnected-(U3-XO-Pad8)") (class "Default")
      (node (ref "U3") (pin "8") (pinfunction "XO_8") (pintype "bidirectional"))
    )
    (net (code "49") (name "unconnected-(U4-A3-Pad4)") (class "Default")
      (node (ref "U4") (pin "4") (pinfunction "A3_4") (pintype "bidirectional"))
    )
    (net (code "50") (name "unconnected-(U4-A4-Pad5)") (class "Default")
      (node (ref "U4") (pin "5") (pinfunction "A4_5") (pintype "bidirectional"))
    )
    (net (code "51") (name "unconnected-(U4-B3-Pad11)") (class "Default")
      (node (ref "U4") (pin "11") (pinfunction "B3_11") (pintype "bidirectional"))
    )
    (net (code "52") (name "unconnected-(U4-B4-Pad10)") (class "Default")
      (node (ref "U4") (pin "10") (pinfunction "B4_10") (pintype "bidirectional"))
    )
  )
)
